# W681.net
KiCad netlist of a schematic drawn in EAGLE
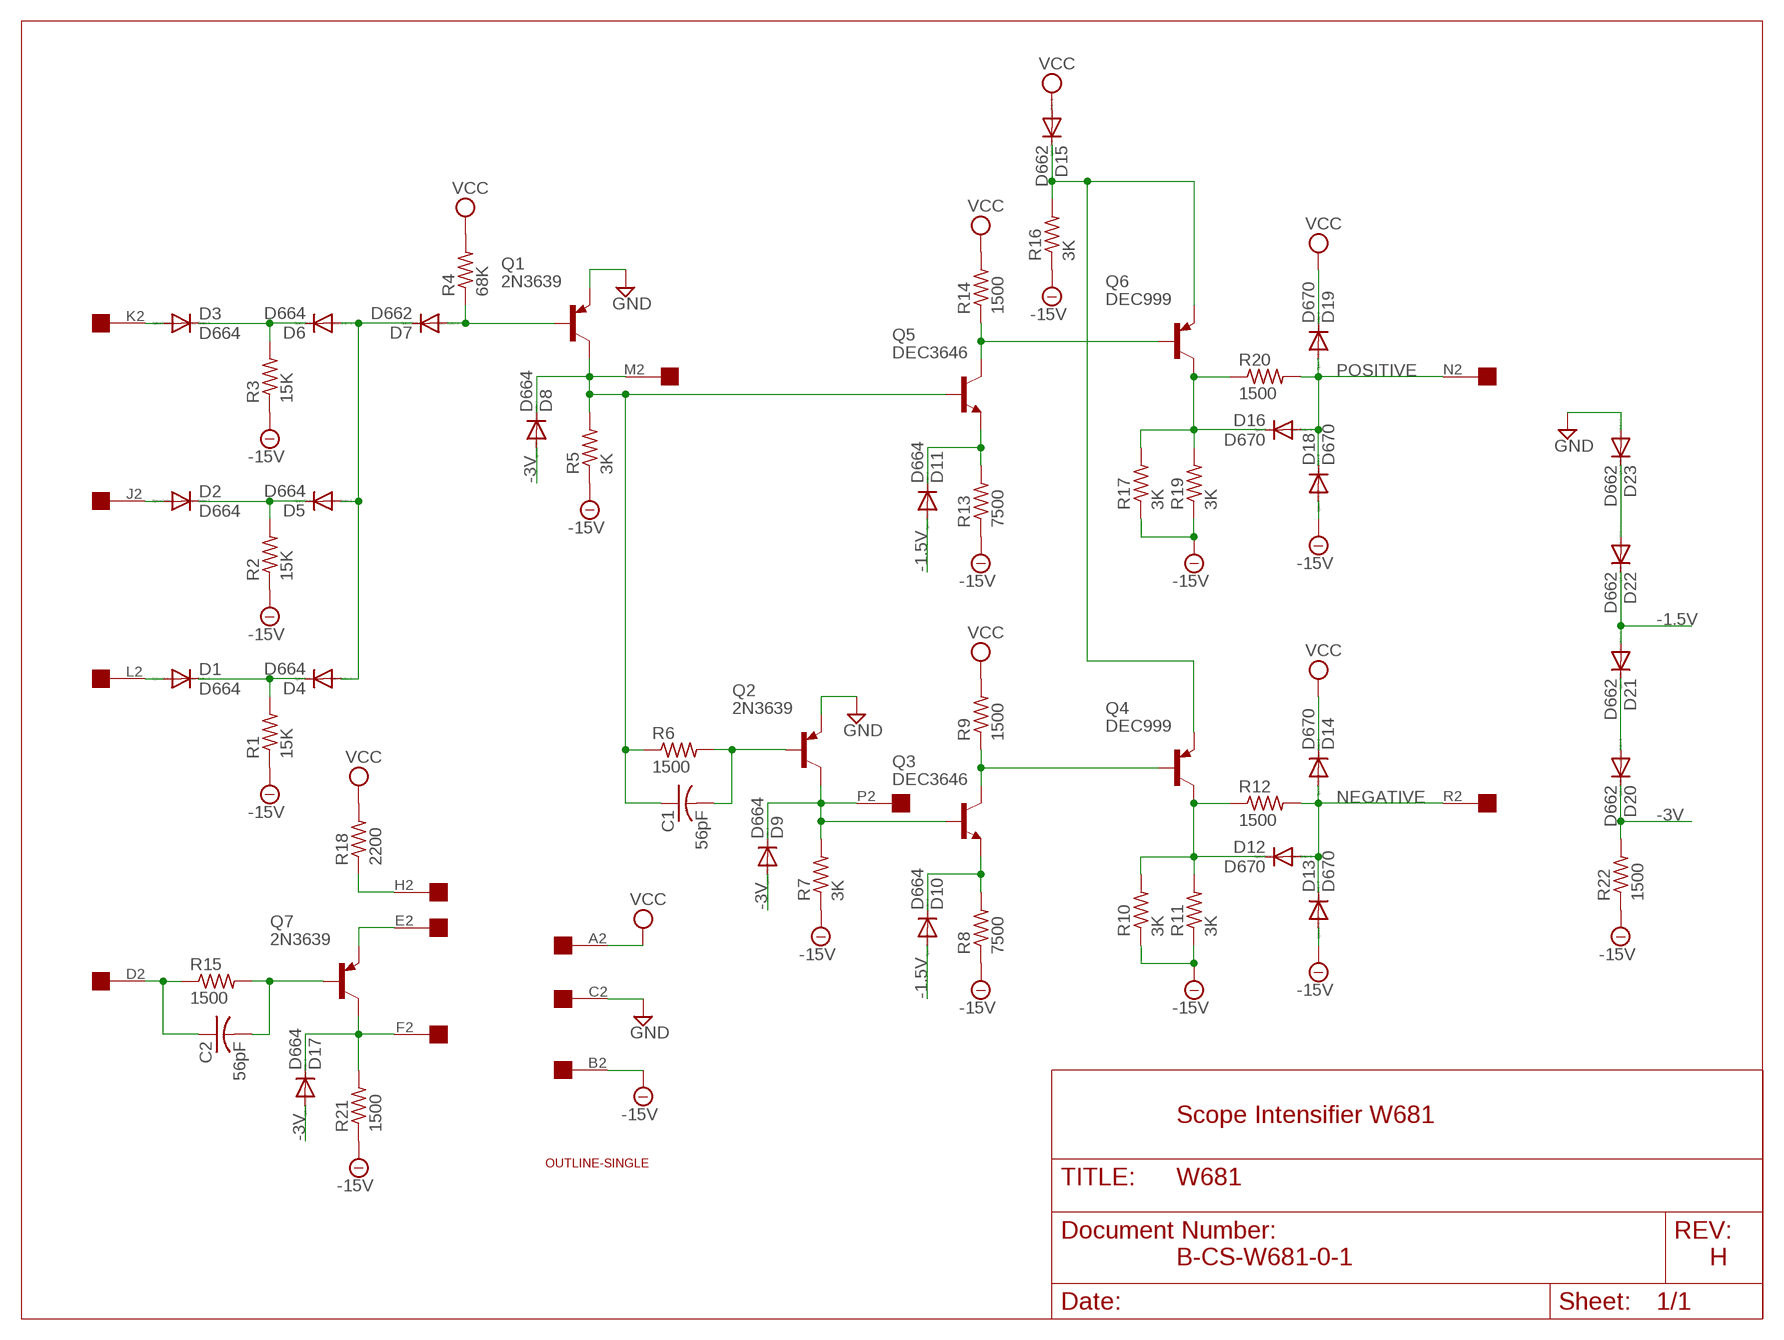
[diagram p0: schematic, sheet 1]

(export (version "E")
  (design (tool "Eeschema 10.0.6"))
  (components
    (comp (ref "C1")
      (value "56pF")
      (footprint "eagle-import:C063-025X075")
      (libsource (lib "eagle-import") (part "C-US"))
    )
    (comp (ref "C2")
      (value "56pF")
      (footprint "eagle-import:C063-025X075")
      (libsource (lib "eagle-import") (part "C-US"))
    )
    (comp (ref "D1")
      (value "D664")
      (footprint "eagle-import:DO35-10")
      (libsource (lib "eagle-import") (part "DIODE-DO35-10"))
    )
    (comp (ref "D2")
      (value "D664")
      (footprint "eagle-import:DO35-10")
      (libsource (lib "eagle-import") (part "DIODE-DO35-10"))
    )
    (comp (ref "D3")
      (value "D664")
      (footprint "eagle-import:DO35-10")
      (libsource (lib "eagle-import") (part "DIODE-DO35-10"))
    )
    (comp (ref "D4")
      (value "D664")
      (footprint "eagle-import:DO35-10")
      (libsource (lib "eagle-import") (part "DIODE-DO35-10"))
    )
    (comp (ref "D5")
      (value "D664")
      (footprint "eagle-import:DO35-10")
      (libsource (lib "eagle-import") (part "DIODE-DO35-10"))
    )
    (comp (ref "D6")
      (value "D664")
      (footprint "eagle-import:DO35-10")
      (libsource (lib "eagle-import") (part "DIODE-DO35-10"))
    )
    (comp (ref "D7")
      (value "D662")
      (footprint "eagle-import:DO35-10")
      (libsource (lib "eagle-import") (part "DIODE-DO35-10"))
    )
    (comp (ref "D8")
      (value "D664")
      (footprint "eagle-import:DO35-10")
      (libsource (lib "eagle-import") (part "DIODE-DO35-10"))
    )
    (comp (ref "D9")
      (value "D664")
      (footprint "eagle-import:DO35-10")
      (libsource (lib "eagle-import") (part "DIODE-DO35-10"))
    )
    (comp (ref "D10")
      (value "D664")
      (footprint "eagle-import:DO35-10")
      (libsource (lib "eagle-import") (part "DIODE-DO35-10"))
    )
    (comp (ref "D11")
      (value "D664")
      (footprint "eagle-import:DO35-10")
      (libsource (lib "eagle-import") (part "DIODE-DO35-10"))
    )
    (comp (ref "D12")
      (value "D670")
      (footprint "eagle-import:DO35-10")
      (libsource (lib "eagle-import") (part "DIODE-DO35-10"))
    )
    (comp (ref "D13")
      (value "D670")
      (footprint "eagle-import:DO35-10")
      (libsource (lib "eagle-import") (part "DIODE-DO35-10"))
    )
    (comp (ref "D14")
      (value "D670")
      (footprint "eagle-import:DO35-10")
      (libsource (lib "eagle-import") (part "DIODE-DO35-10"))
    )
    (comp (ref "D15")
      (value "D662")
      (footprint "eagle-import:DO35-10")
      (libsource (lib "eagle-import") (part "DIODE-DO35-10"))
    )
    (comp (ref "D16")
      (value "D670")
      (footprint "eagle-import:DO35-10")
      (libsource (lib "eagle-import") (part "DIODE-DO35-10"))
    )
    (comp (ref "D17")
      (value "D664")
      (footprint "eagle-import:DO35-10")
      (libsource (lib "eagle-import") (part "DIODE-DO35-10"))
    )
    (comp (ref "D18")
      (value "D670")
      (footprint "eagle-import:DO35-10")
      (libsource (lib "eagle-import") (part "DIODE-DO35-10"))
    )
    (comp (ref "D19")
      (value "D670")
      (footprint "eagle-import:DO35-10")
      (libsource (lib "eagle-import") (part "DIODE-DO35-10"))
    )
    (comp (ref "D20")
      (value "D662")
      (footprint "eagle-import:DO35-10")
      (libsource (lib "eagle-import") (part "DIODE-DO35-10"))
    )
    (comp (ref "D21")
      (value "D662")
      (footprint "eagle-import:DO35-10")
      (libsource (lib "eagle-import") (part "DIODE-DO35-10"))
    )
    (comp (ref "D22")
      (value "D662")
      (footprint "eagle-import:DO35-10")
      (libsource (lib "eagle-import") (part "DIODE-DO35-10"))
    )
    (comp (ref "D23")
      (value "D662")
      (footprint "eagle-import:DO35-10")
      (libsource (lib "eagle-import") (part "DIODE-DO35-10"))
    )
    (comp (ref "Q1")
      (value "2N3639")
      (footprint "eagle-import:TO5")
      (libsource (lib "eagle-import") (part "-PNP-TO5"))
    )
    (comp (ref "Q2")
      (value "2N3639")
      (footprint "eagle-import:TO5")
      (libsource (lib "eagle-import") (part "-PNP-TO5"))
    )
    (comp (ref "Q3")
      (value "DEC3646")
      (footprint "eagle-import:TO5")
      (libsource (lib "eagle-import") (part "-NPN-TO5"))
    )
    (comp (ref "Q4")
      (value "DEC999")
      (footprint "eagle-import:TO5")
      (libsource (lib "eagle-import") (part "-PNP-TO5"))
    )
    (comp (ref "Q5")
      (value "DEC3646")
      (footprint "eagle-import:TO5")
      (libsource (lib "eagle-import") (part "-NPN-TO5"))
    )
    (comp (ref "Q6")
      (value "DEC999")
      (footprint "eagle-import:TO5")
      (libsource (lib "eagle-import") (part "-PNP-TO5"))
    )
    (comp (ref "Q7")
      (value "2N3639")
      (footprint "eagle-import:TO5")
      (libsource (lib "eagle-import") (part "-PNP-TO5"))
    )
    (comp (ref "R1")
      (value "15K")
      (footprint "eagle-import:0207_10")
      (libsource (lib "eagle-import") (part "R-US_0207/10"))
    )
    (comp (ref "R2")
      (value "15K")
      (footprint "eagle-import:0207_10")
      (libsource (lib "eagle-import") (part "R-US_0207/10"))
    )
    (comp (ref "R3")
      (value "15K")
      (footprint "eagle-import:0207_10")
      (libsource (lib "eagle-import") (part "R-US_0207/10"))
    )
    (comp (ref "R4")
      (value "68K")
      (footprint "eagle-import:0207_10")
      (libsource (lib "eagle-import") (part "R-US_0207/10"))
    )
    (comp (ref "R5")
      (value "3K")
      (footprint "eagle-import:0207_10")
      (libsource (lib "eagle-import") (part "R-US_0207/10"))
    )
    (comp (ref "R6")
      (value "1500")
      (footprint "eagle-import:0207_10")
      (libsource (lib "eagle-import") (part "R-US_0207/10"))
    )
    (comp (ref "R7")
      (value "3K")
      (footprint "eagle-import:0207_10")
      (libsource (lib "eagle-import") (part "R-US_0207/10"))
    )
    (comp (ref "R8")
      (value "7500")
      (footprint "eagle-import:0207_10")
      (libsource (lib "eagle-import") (part "R-US_0207/10"))
    )
    (comp (ref "R9")
      (value "1500")
      (footprint "eagle-import:0207_10")
      (libsource (lib "eagle-import") (part "R-US_0207/10"))
    )
    (comp (ref "R10")
      (value "3K")
      (footprint "eagle-import:0207_10")
      (libsource (lib "eagle-import") (part "R-US_0207/10"))
    )
    (comp (ref "R11")
      (value "3K")
      (footprint "eagle-import:0207_10")
      (libsource (lib "eagle-import") (part "R-US_0207/10"))
    )
    (comp (ref "R12")
      (value "1500")
      (footprint "eagle-import:0207_10")
      (libsource (lib "eagle-import") (part "R-US_0207/10"))
    )
    (comp (ref "R13")
      (value "7500")
      (footprint "eagle-import:0207_10")
      (libsource (lib "eagle-import") (part "R-US_0207/10"))
    )
    (comp (ref "R14")
      (value "1500")
      (footprint "eagle-import:0207_10")
      (libsource (lib "eagle-import") (part "R-US_0207/10"))
    )
    (comp (ref "R15")
      (value "1500")
      (footprint "eagle-import:0207_10")
      (libsource (lib "eagle-import") (part "R-US_0207/10"))
    )
    (comp (ref "R16")
      (value "3K")
      (footprint "eagle-import:0207_10")
      (libsource (lib "eagle-import") (part "R-US_0207/10"))
    )
    (comp (ref "R17")
      (value "3K")
      (footprint "eagle-import:0207_10")
      (libsource (lib "eagle-import") (part "R-US_0207/10"))
    )
    (comp (ref "R18")
      (value "2200")
      (footprint "eagle-import:0207_10")
      (libsource (lib "eagle-import") (part "R-US_0207/10"))
    )
    (comp (ref "R19")
      (value "3K")
      (footprint "eagle-import:0207_10")
      (libsource (lib "eagle-import") (part "R-US_0207/10"))
    )
    (comp (ref "R20")
      (value "1500")
      (footprint "eagle-import:0207_10")
      (libsource (lib "eagle-import") (part "R-US_0207/10"))
    )
    (comp (ref "R21")
      (value "1500")
      (footprint "eagle-import:0207_10")
      (libsource (lib "eagle-import") (part "R-US_0207/10"))
    )
    (comp (ref "R22")
      (value "1500")
      (footprint "eagle-import:0207_10")
      (libsource (lib "eagle-import") (part "R-US_0207/10"))
    )
    (comp (ref "U$1")
      (value "OUTLINE-SINGLE")
      (footprint "eagle-import:SINGLE")
      (libsource (lib "eagle-import") (part "OUTLINE-SINGLE"))
    )
    (comp (ref "U$2")
      (value "EDGE-1")
      (footprint "eagle-import:EDGE-CON1")
      (libsource (lib "eagle-import") (part "EDGE-1"))
    )
  )
  (nets
    (net (code "1") (name "-15V") (class "Default")
      (node (ref "D13") (pin "A") (pinfunction "A_A") (pintype "passive"))
      (node (ref "D18") (pin "A") (pinfunction "A_A") (pintype "passive"))
      (node (ref "R1") (pin "1") (pinfunction "1_1") (pintype "passive"))
      (node (ref "R10") (pin "1") (pinfunction "1_1") (pintype "passive"))
      (node (ref "R11") (pin "1") (pinfunction "1_1") (pintype "passive"))
      (node (ref "R13") (pin "1") (pinfunction "1_1") (pintype "passive"))
      (node (ref "R16") (pin "1") (pinfunction "1_1") (pintype "passive"))
      (node (ref "R17") (pin "1") (pinfunction "1_1") (pintype "passive"))
      (node (ref "R19") (pin "1") (pinfunction "1_1") (pintype "passive"))
      (node (ref "R2") (pin "1") (pinfunction "1_1") (pintype "passive"))
      (node (ref "R21") (pin "1") (pinfunction "1_1") (pintype "passive"))
      (node (ref "R22") (pin "1") (pinfunction "1_1") (pintype "passive"))
      (node (ref "R3") (pin "1") (pinfunction "1_1") (pintype "passive"))
      (node (ref "R5") (pin "1") (pinfunction "1_1") (pintype "passive"))
      (node (ref "R7") (pin "1") (pinfunction "1_1") (pintype "passive"))
      (node (ref "R8") (pin "1") (pinfunction "1_1") (pintype "passive"))
      (node (ref "U$2") (pin "B2") (pinfunction "1_B2") (pintype "bidirectional"))
    )
    (net (code "2") (name "/-1.5V") (class "Default")
      (node (ref "D10") (pin "A") (pinfunction "A_A") (pintype "passive"))
      (node (ref "D11") (pin "A") (pinfunction "A_A") (pintype "passive"))
      (node (ref "D21") (pin "A") (pinfunction "A_A") (pintype "passive"))
      (node (ref "D22") (pin "C") (pinfunction "C_C") (pintype "passive"))
    )
    (net (code "3") (name "/-3V") (class "Default")
      (node (ref "D17") (pin "A") (pinfunction "A_A") (pintype "passive"))
      (node (ref "D20") (pin "C") (pinfunction "C_C") (pintype "passive"))
      (node (ref "D8") (pin "A") (pinfunction "A_A") (pintype "passive"))
      (node (ref "D9") (pin "A") (pinfunction "A_A") (pintype "passive"))
      (node (ref "R22") (pin "2") (pinfunction "2_2") (pintype "passive"))
    )
    (net (code "4") (name "/NEGATIVE") (class "Default")
      (node (ref "D12") (pin "A") (pinfunction "A_A") (pintype "passive"))
      (node (ref "D13") (pin "C") (pinfunction "C_C") (pintype "passive"))
      (node (ref "D14") (pin "A") (pinfunction "A_A") (pintype "passive"))
      (node (ref "R12") (pin "2") (pinfunction "2_2") (pintype "passive"))
      (node (ref "U$2") (pin "R2") (pinfunction "1_R2") (pintype "bidirectional"))
    )
    (net (code "5") (name "/POSITIVE") (class "Default")
      (node (ref "D16") (pin "A") (pinfunction "A_A") (pintype "passive"))
      (node (ref "D18") (pin "C") (pinfunction "C_C") (pintype "passive"))
      (node (ref "D19") (pin "A") (pinfunction "A_A") (pintype "passive"))
      (node (ref "R20") (pin "2") (pinfunction "2_2") (pintype "passive"))
      (node (ref "U$2") (pin "N2") (pinfunction "1_N2") (pintype "bidirectional"))
    )
    (net (code "6") (name "GND") (class "Default")
      (node (ref "D23") (pin "A") (pinfunction "A_A") (pintype "passive"))
      (node (ref "Q1") (pin "1") (pinfunction "E_1") (pintype "passive"))
      (node (ref "Q2") (pin "1") (pinfunction "E_1") (pintype "passive"))
      (node (ref "U$2") (pin "C2") (pinfunction "1_C2") (pintype "bidirectional"))
    )
    (net (code "7") (name "Net-(D1-PadC)") (class "Default")
      (node (ref "D1") (pin "C") (pinfunction "C_C") (pintype "passive"))
      (node (ref "D4") (pin "C") (pinfunction "C_C") (pintype "passive"))
      (node (ref "R1") (pin "2") (pinfunction "2_2") (pintype "passive"))
    )
    (net (code "8") (name "Net-(D2-PadC)") (class "Default")
      (node (ref "D2") (pin "C") (pinfunction "C_C") (pintype "passive"))
      (node (ref "D5") (pin "C") (pinfunction "C_C") (pintype "passive"))
      (node (ref "R2") (pin "2") (pinfunction "2_2") (pintype "passive"))
    )
    (net (code "9") (name "Net-(D3-PadC)") (class "Default")
      (node (ref "D3") (pin "C") (pinfunction "C_C") (pintype "passive"))
      (node (ref "D6") (pin "C") (pinfunction "C_C") (pintype "passive"))
      (node (ref "R3") (pin "2") (pinfunction "2_2") (pintype "passive"))
    )
    (net (code "10") (name "Net-(D4-PadA)") (class "Default")
      (node (ref "D4") (pin "A") (pinfunction "A_A") (pintype "passive"))
      (node (ref "D5") (pin "A") (pinfunction "A_A") (pintype "passive"))
      (node (ref "D6") (pin "A") (pinfunction "A_A") (pintype "passive"))
      (node (ref "D7") (pin "C") (pinfunction "C_C") (pintype "passive"))
    )
    (net (code "11") (name "Net-(D20-PadA)") (class "Default")
      (node (ref "D20") (pin "A") (pinfunction "A_A") (pintype "passive"))
      (node (ref "D21") (pin "C") (pinfunction "C_C") (pintype "passive"))
    )
    (net (code "12") (name "Net-(D22-PadA)") (class "Default")
      (node (ref "D22") (pin "A") (pinfunction "A_A") (pintype "passive"))
      (node (ref "D23") (pin "C") (pinfunction "C_C") (pintype "passive"))
    )
    (net (code "13") (name "Net-(Q1-B)") (class "Default")
      (node (ref "D7") (pin "A") (pinfunction "A_A") (pintype "passive"))
      (node (ref "Q1") (pin "2") (pinfunction "B_2") (pintype "passive"))
      (node (ref "R4") (pin "1") (pinfunction "1_1") (pintype "passive"))
    )
    (net (code "14") (name "Net-(Q1-C)") (class "Default")
      (node (ref "C1") (pin "1") (pinfunction "1_1") (pintype "passive"))
      (node (ref "D8") (pin "C") (pinfunction "C_C") (pintype "passive"))
      (node (ref "Q1") (pin "3") (pinfunction "C_3") (pintype "passive"))
      (node (ref "Q5") (pin "2") (pinfunction "B_2") (pintype "passive"))
      (node (ref "R5") (pin "2") (pinfunction "2_2") (pintype "passive"))
      (node (ref "R6") (pin "1") (pinfunction "1_1") (pintype "passive"))
      (node (ref "U$2") (pin "M2") (pinfunction "1_M2") (pintype "bidirectional"))
    )
    (net (code "15") (name "Net-(Q2-B)") (class "Default")
      (node (ref "C1") (pin "2") (pinfunction "2_2") (pintype "passive"))
      (node (ref "Q2") (pin "2") (pinfunction "B_2") (pintype "passive"))
      (node (ref "R6") (pin "2") (pinfunction "2_2") (pintype "passive"))
    )
    (net (code "16") (name "Net-(Q2-C)") (class "Default")
      (node (ref "D9") (pin "C") (pinfunction "C_C") (pintype "passive"))
      (node (ref "Q2") (pin "3") (pinfunction "C_3") (pintype "passive"))
      (node (ref "Q3") (pin "2") (pinfunction "B_2") (pintype "passive"))
      (node (ref "R7") (pin "2") (pinfunction "2_2") (pintype "passive"))
      (node (ref "U$2") (pin "P2") (pinfunction "1_P2") (pintype "bidirectional"))
    )
    (net (code "17") (name "Net-(Q3-C)") (class "Default")
      (node (ref "Q3") (pin "3") (pinfunction "C_3") (pintype "passive"))
      (node (ref "Q4") (pin "2") (pinfunction "B_2") (pintype "passive"))
      (node (ref "R9") (pin "1") (pinfunction "1_1") (pintype "passive"))
    )
    (net (code "18") (name "Net-(Q3-E)") (class "Default")
      (node (ref "D10") (pin "C") (pinfunction "C_C") (pintype "passive"))
      (node (ref "Q3") (pin "1") (pinfunction "E_1") (pintype "passive"))
      (node (ref "R8") (pin "2") (pinfunction "2_2") (pintype "passive"))
    )
    (net (code "19") (name "Net-(Q4-C)") (class "Default")
      (node (ref "D12") (pin "C") (pinfunction "C_C") (pintype "passive"))
      (node (ref "Q4") (pin "3") (pinfunction "C_3") (pintype "passive"))
      (node (ref "R10") (pin "2") (pinfunction "2_2") (pintype "passive"))
      (node (ref "R11") (pin "2") (pinfunction "2_2") (pintype "passive"))
      (node (ref "R12") (pin "1") (pinfunction "1_1") (pintype "passive"))
    )
    (net (code "20") (name "Net-(Q4-E)") (class "Default")
      (node (ref "D15") (pin "C") (pinfunction "C_C") (pintype "passive"))
      (node (ref "Q4") (pin "1") (pinfunction "E_1") (pintype "passive"))
      (node (ref "Q6") (pin "1") (pinfunction "E_1") (pintype "passive"))
      (node (ref "R16") (pin "2") (pinfunction "2_2") (pintype "passive"))
    )
    (net (code "21") (name "Net-(Q5-C)") (class "Default")
      (node (ref "Q5") (pin "3") (pinfunction "C_3") (pintype "passive"))
      (node (ref "Q6") (pin "2") (pinfunction "B_2") (pintype "passive"))
      (node (ref "R14") (pin "1") (pinfunction "1_1") (pintype "passive"))
    )
    (net (code "22") (name "Net-(Q5-E)") (class "Default")
      (node (ref "D11") (pin "C") (pinfunction "C_C") (pintype "passive"))
      (node (ref "Q5") (pin "1") (pinfunction "E_1") (pintype "passive"))
      (node (ref "R13") (pin "2") (pinfunction "2_2") (pintype "passive"))
    )
    (net (code "23") (name "Net-(Q6-C)") (class "Default")
      (node (ref "D16") (pin "C") (pinfunction "C_C") (pintype "passive"))
      (node (ref "Q6") (pin "3") (pinfunction "C_3") (pintype "passive"))
      (node (ref "R17") (pin "2") (pinfunction "2_2") (pintype "passive"))
      (node (ref "R19") (pin "2") (pinfunction "2_2") (pintype "passive"))
      (node (ref "R20") (pin "1") (pinfunction "1_1") (pintype "passive"))
    )
    (net (code "24") (name "Net-(Q7-B)") (class "Default")
      (node (ref "C2") (pin "2") (pinfunction "2_2") (pintype "passive"))
      (node (ref "Q7") (pin "2") (pinfunction "B_2") (pintype "passive"))
      (node (ref "R15") (pin "2") (pinfunction "2_2") (pintype "passive"))
    )
    (net (code "25") (name "Net-(Q7-C)") (class "Default")
      (node (ref "D17") (pin "C") (pinfunction "C_C") (pintype "passive"))
      (node (ref "Q7") (pin "3") (pinfunction "C_3") (pintype "passive"))
      (node (ref "R21") (pin "2") (pinfunction "2_2") (pintype "passive"))
      (node (ref "U$2") (pin "F2") (pinfunction "1_F2") (pintype "bidirectional"))
    )
    (net (code "26") (name "Net-(Q7-E)") (class "Default")
      (node (ref "Q7") (pin "1") (pinfunction "E_1") (pintype "passive"))
      (node (ref "U$2") (pin "E2") (pinfunction "1_E2") (pintype "bidirectional"))
    )
    (net (code "27") (name "Net-(U$2D-1)") (class "Default")
      (node (ref "C2") (pin "1") (pinfunction "1_1") (pintype "passive"))
      (node (ref "R15") (pin "1") (pinfunction "1_1") (pintype "passive"))
      (node (ref "U$2") (pin "D2") (pinfunction "1_D2") (pintype "bidirectional"))
    )
    (net (code "28") (name "Net-(U$2G-1)") (class "Default")
      (node (ref "R18") (pin "1") (pinfunction "1_1") (pintype "passive"))
      (node (ref "U$2") (pin "H2") (pinfunction "1_H2") (pintype "bidirectional"))
    )
    (net (code "29") (name "Net-(U$2H-1)") (class "Default")
      (node (ref "D2") (pin "A") (pinfunction "A_A") (pintype "passive"))
      (node (ref "U$2") (pin "J2") (pinfunction "1_J2") (pintype "bidirectional"))
    )
    (net (code "30") (name "Net-(U$2I-1)") (class "Default")
      (node (ref "D3") (pin "A") (pinfunction "A_A") (pintype "passive"))
      (node (ref "U$2") (pin "K2") (pinfunction "1_K2") (pintype "bidirectional"))
    )
    (net (code "31") (name "Net-(U$2J-1)") (class "Default")
      (node (ref "D1") (pin "A") (pinfunction "A_A") (pintype "passive"))
      (node (ref "U$2") (pin "L2") (pinfunction "1_L2") (pintype "bidirectional"))
    )
    (net (code "32") (name "VCC") (class "Default")
      (node (ref "D14") (pin "C") (pinfunction "C_C") (pintype "passive"))
      (node (ref "D15") (pin "A") (pinfunction "A_A") (pintype "passive"))
      (node (ref "D19") (pin "C") (pinfunction "C_C") (pintype "passive"))
      (node (ref "R14") (pin "2") (pinfunction "2_2") (pintype "passive"))
      (node (ref "R18") (pin "2") (pinfunction "2_2") (pintype "passive"))
      (node (ref "R4") (pin "2") (pinfunction "2_2") (pintype "passive"))
      (node (ref "R9") (pin "2") (pinfunction "2_2") (pintype "passive"))
      (node (ref "U$2") (pin "A2") (pinfunction "1_A2") (pintype "bidirectional"))
    )
  )
)
